# ctrl-brd.net
KiCad netlist of a schematic drawn in EAGLE
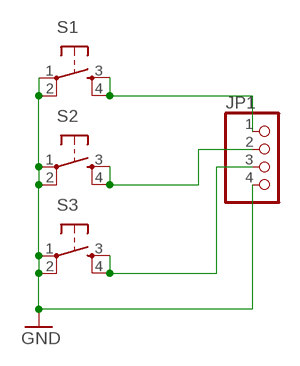
[diagram p0: schematic, sheet 1]

(export (version "E")
  (design (tool "Eeschema 10.0.6"))
  (components
    (comp (ref "JP1")
      (value "PINHD-1X4")
      (footprint "eagle-import:1X04")
      (libsource (lib "eagle-import") (part "PINHD-1X4"))
    )
    (comp (ref "S1")
      (value "6MM_SWITCH6MM_SWITCH")
      (footprint "eagle-import:6MM_SWITCH")
      (libsource (lib "eagle-import") (part "6MM_SWITCH6MM_SWITCH"))
    )
    (comp (ref "S2")
      (value "6MM_SWITCH6MM_SWITCH")
      (footprint "eagle-import:6MM_SWITCH")
      (libsource (lib "eagle-import") (part "6MM_SWITCH6MM_SWITCH"))
    )
    (comp (ref "S3")
      (value "6MM_SWITCH6MM_SWITCH")
      (footprint "eagle-import:6MM_SWITCH")
      (libsource (lib "eagle-import") (part "6MM_SWITCH6MM_SWITCH"))
    )
  )
  (nets
    (net (code "1") (name "GND") (class "Default")
      (node (ref "JP1") (pin "4") (pinfunction "4_4") (pintype "passive"))
      (node (ref "S1") (pin "1") (pinfunction "P_1") (pintype "passive"))
      (node (ref "S1") (pin "2") (pinfunction "P1_2") (pintype "passive"))
      (node (ref "S2") (pin "1") (pinfunction "P_1") (pintype "passive"))
      (node (ref "S2") (pin "2") (pinfunction "P1_2") (pintype "passive"))
      (node (ref "S3") (pin "1") (pinfunction "P_1") (pintype "passive"))
      (node (ref "S3") (pin "2") (pinfunction "P1_2") (pintype "passive"))
    )
    (net (code "2") (name "Net-(S1-S)") (class "Default")
      (node (ref "JP1") (pin "1") (pinfunction "1_1") (pintype "passive"))
      (node (ref "S1") (pin "3") (pinfunction "S_3") (pintype "passive"))
      (node (ref "S1") (pin "4") (pinfunction "S1_4") (pintype "passive"))
    )
    (net (code "3") (name "Net-(S2-S)") (class "Default")
      (node (ref "JP1") (pin "2") (pinfunction "2_2") (pintype "passive"))
      (node (ref "S2") (pin "3") (pinfunction "S_3") (pintype "passive"))
      (node (ref "S2") (pin "4") (pinfunction "S1_4") (pintype "passive"))
    )
    (net (code "4") (name "Net-(S3-S)") (class "Default")
      (node (ref "JP1") (pin "3") (pinfunction "3_3") (pintype "passive"))
      (node (ref "S3") (pin "3") (pinfunction "S_3") (pintype "passive"))
      (node (ref "S3") (pin "4") (pinfunction "S1_4") (pintype "passive"))
    )
  )
)
